# TR.net
KiCad netlist of a schematic drawn in Altium Designer
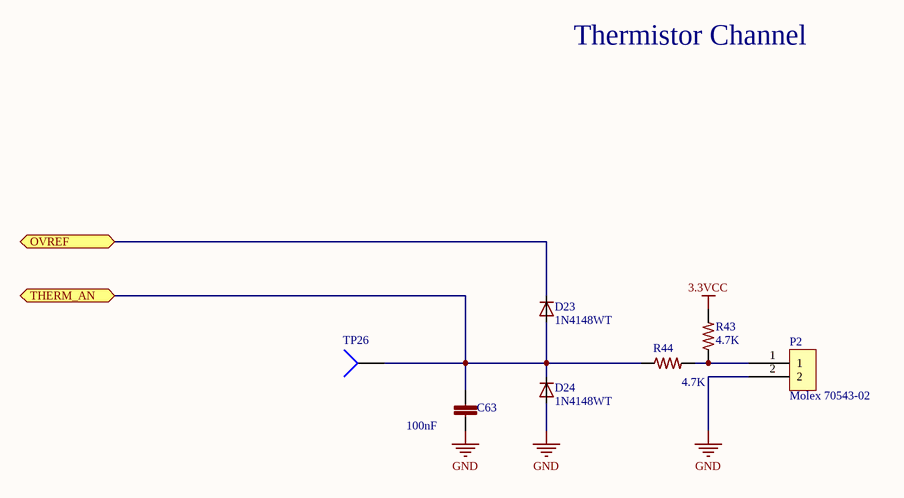
[diagram p0: TR.SchDoc]

(export (version "E")
  (design (tool "Eeschema 10.0.6"))
  (components
    (comp (ref "C63")
      (value "100nF")
      (footprint "C0402")
      (description "CAP CER 0402 100nF 16V 10% X7R")
      (fields
        (field (name "MANUFACTURERPARTNUMBER") "GRM155R71C104KA88D")
        (field (name "PUBLISHER") "UltiMachine")
      )
      (libsource (lib "3Delight") (part "GRM155R71C104KA88D"))
    )
    (comp (ref "D23")
      (value "1N4148WT")
      (footprint "SOD523")
      (description "DIODE SOD523")
      (fields (field (name "PUBLISHER") "UltiMachine"))
      (libsource (lib "Tigershark3D") (part "1N4148WT"))
    )
    (comp (ref "D24")
      (value "1N4148WT")
      (footprint "SOD523")
      (description "DIODE SOD523")
      (fields (field (name "PUBLISHER") "UltiMachine"))
      (libsource (lib "Tigershark3D") (part "1N4148WT"))
    )
    (comp (ref "P2")
      (value "Molex 70543-02")
      (footprint "70543-02")
      (libsource (lib "ZMBo Schematic Library") (part "Molex 70543-02"))
    )
    (comp (ref "R43")
      (value "4.7K")
      (footprint "R0603")
      (description "RES 0603 4.7K 100mW 1%")
      (fields (field (name "MANUFACTURERPARTNUMBER") "ERJ3EKF4701V") (field (name "PUBLISHER") "UltiMachine"))
      (libsource (lib "3Delight") (part "ERJ3EKF4701V"))
    )
    (comp (ref "R44")
      (value "4.7K")
      (footprint "R0603")
      (description "RES 0603 4.7K 100mW 1%")
      (fields (field (name "MANUFACTURERPARTNUMBER") "ERJ3EKF4701V") (field (name "PUBLISHER") "UltiMachine"))
      (libsource (lib "3Delight") (part "ERJ3EKF4701V"))
    )
    (comp (ref "TP26")
      (value "TP4")
      (footprint "TP-2")
      (description "Socket")
      (fields (field (name "PUBLISHER") "Altium Limited"))
      (libsource (lib "ZMBo Schematic Library") (part "Socket"))
    )
  )
  (nets
    (net (code "1") (name "/OVREF") (class "Default")
      (node (ref "D23") (pin "C") (pinfunction "C_C") (pintype "passive"))
    )
    (net (code "2") (name "/THERM_AN") (class "Default")
      (node (ref "C63") (pin "1") (pinfunction "1_1") (pintype "passive"))
      (node (ref "D23") (pin "A") (pinfunction "A_A") (pintype "passive"))
      (node (ref "D24") (pin "C") (pinfunction "C_C") (pintype "passive"))
      (node (ref "R44") (pin "1") (pinfunction "1_1") (pintype "passive"))
      (node (ref "TP26") (pin "1") (pinfunction "1_1") (pintype "passive"))
    )
    (net (code "3") (name "3.3VCC") (class "Default")
      (node (ref "R43") (pin "2") (pinfunction "2_2") (pintype "passive"))
    )
    (net (code "4") (name "GND") (class "Default")
      (node (ref "C63") (pin "2") (pinfunction "2_2") (pintype "passive"))
      (node (ref "D24") (pin "A") (pinfunction "A_A") (pintype "passive"))
      (node (ref "P2") (pin "2") (pinfunction "2_2") (pintype "passive"))
    )
    (net (code "5") (name "Net-(P2-Pad1)") (class "Default")
      (node (ref "P2") (pin "1") (pinfunction "1_1") (pintype "passive"))
      (node (ref "R43") (pin "1") (pinfunction "1_1") (pintype "passive"))
      (node (ref "R44") (pin "2") (pinfunction "2_2") (pintype "passive"))
    )
  )
)
